# me_433_hw2.net
KiCad netlist of a schematic drawn in EAGLE
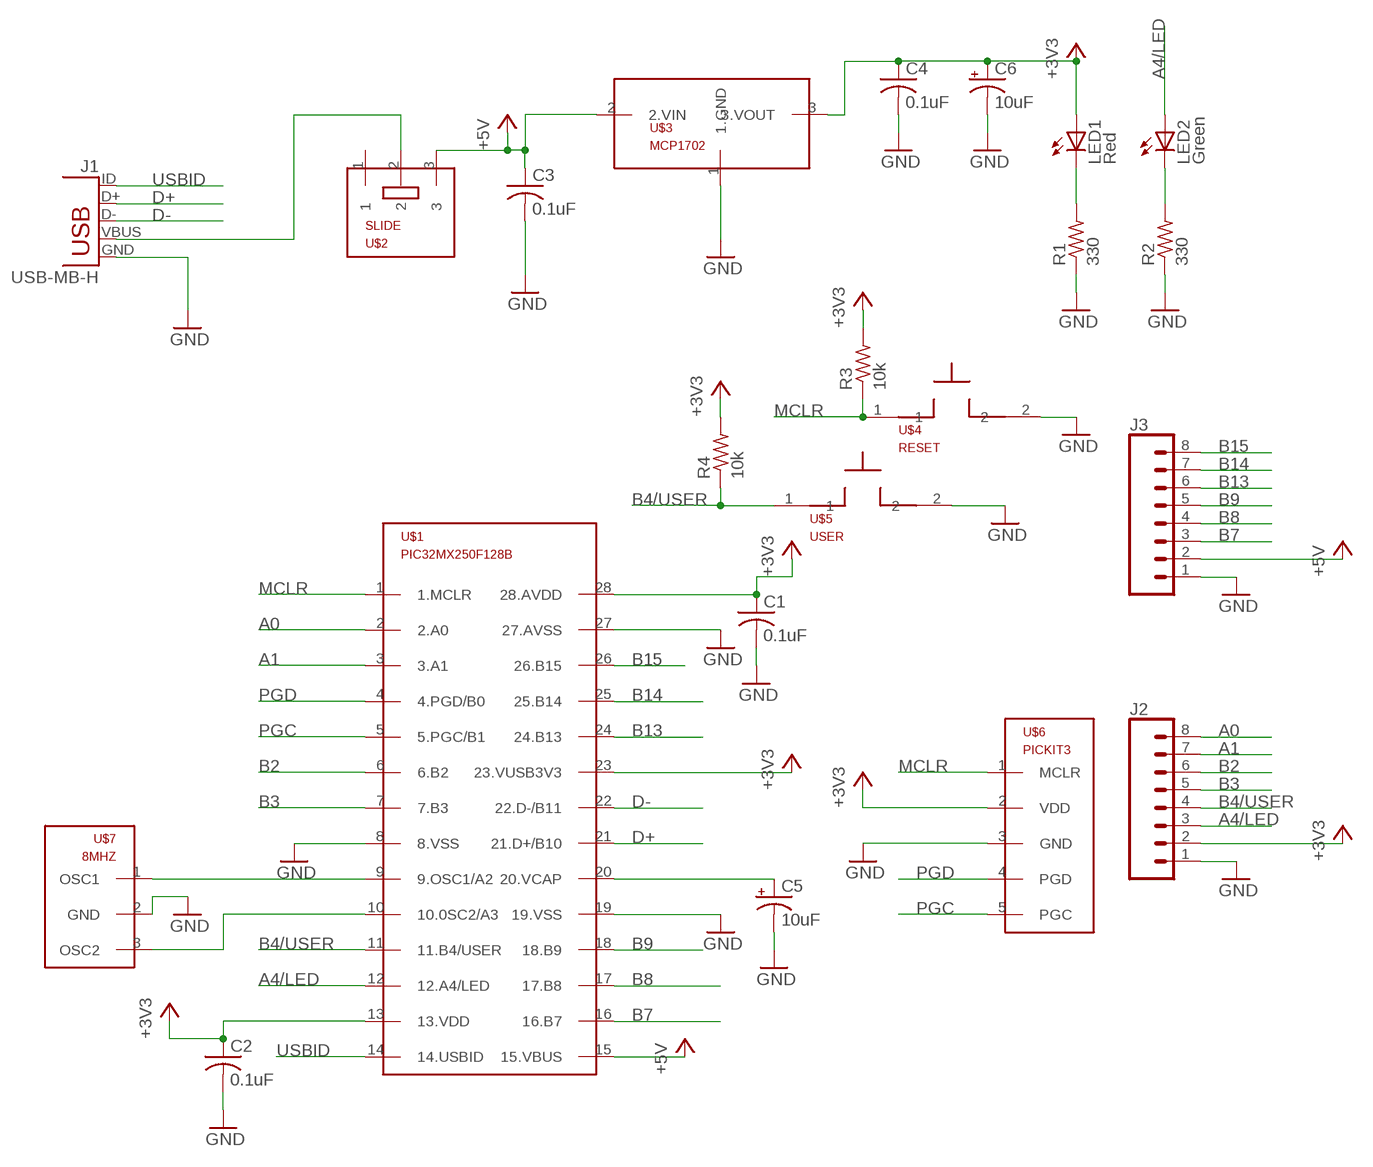
[diagram p0: schematic, sheet 1]

(export (version "E")
  (design (tool "Eeschema 10.0.6"))
  (components
    (comp (ref "C1")
      (value "0.1uF")
      (footprint "eagle-import:C025-025X050")
      (libsource (lib "eagle-import") (part "C-US025-025X050"))
    )
    (comp (ref "C2")
      (value "0.1uF")
      (footprint "eagle-import:C025-025X050")
      (libsource (lib "eagle-import") (part "C-US025-025X050"))
    )
    (comp (ref "C3")
      (value "0.1uF")
      (footprint "eagle-import:C025-025X050")
      (libsource (lib "eagle-import") (part "C-US025-025X050"))
    )
    (comp (ref "C4")
      (value "0.1uF")
      (footprint "eagle-import:C025-025X050")
      (libsource (lib "eagle-import") (part "C-US025-025X050"))
    )
    (comp (ref "C5")
      (value "10uF")
      (footprint "eagle-import:B45181B")
      (libsource (lib "eagle-import") (part "CPOL-USB45181B"))
    )
    (comp (ref "C6")
      (value "10uF")
      (footprint "eagle-import:B45181B")
      (libsource (lib "eagle-import") (part "CPOL-USB45181B"))
    )
    (comp (ref "J1")
      (value "USB-MB-H")
      (footprint "eagle-import:USB-MB-H")
      (libsource (lib "eagle-import") (part "USB-MB-H"))
    )
    (comp (ref "J2")
      (value "CONN_08")
      (footprint "eagle-import:1X08")
      (libsource (lib "eagle-import") (part "CONN_08"))
    )
    (comp (ref "J3")
      (value "CONN_08")
      (footprint "eagle-import:1X08")
      (libsource (lib "eagle-import") (part "CONN_08"))
    )
    (comp (ref "LED1")
      (value "Red")
      (footprint "eagle-import:LED3MM")
      (libsource (lib "eagle-import") (part "LED3MM"))
    )
    (comp (ref "LED2")
      (value "Green")
      (footprint "eagle-import:LED3MM")
      (libsource (lib "eagle-import") (part "LED3MM"))
    )
    (comp (ref "R1")
      (value "330")
      (footprint "eagle-import:0207_10")
      (libsource (lib "eagle-import") (part "R-US_0207/10"))
    )
    (comp (ref "R2")
      (value "330")
      (footprint "eagle-import:0207_10")
      (libsource (lib "eagle-import") (part "R-US_0207/10"))
    )
    (comp (ref "R3")
      (value "10k")
      (footprint "eagle-import:0207_10")
      (libsource (lib "eagle-import") (part "R-US_0207/10"))
    )
    (comp (ref "R4")
      (value "10k")
      (footprint "eagle-import:0207_10")
      (libsource (lib "eagle-import") (part "R-US_0207/10"))
    )
    (comp (ref "U$1")
      (value "PIC32MX250F128B")
      (footprint "eagle-import:DIL28-3")
      (libsource (lib "eagle-import") (part "PIC32MX250F128B"))
    )
    (comp (ref "U$2")
      (value "SLIDE")
      (footprint "eagle-import:SLIDE")
      (libsource (lib "eagle-import") (part "SLIDE"))
    )
    (comp (ref "U$3")
      (value "MCP1702")
      (footprint "eagle-import:TO92")
      (libsource (lib "eagle-import") (part "MCP1702"))
    )
    (comp (ref "U$4")
      (value "RESET")
      (footprint "eagle-import:PB")
      (libsource (lib "eagle-import") (part "PB"))
    )
    (comp (ref "U$5")
      (value "USER")
      (footprint "eagle-import:PB")
      (libsource (lib "eagle-import") (part "PB"))
    )
    (comp (ref "U$6")
      (value "PICKIT3")
      (footprint "eagle-import:1X05")
      (libsource (lib "eagle-import") (part "PICKIT3"))
    )
    (comp (ref "U$7")
      (value "8MHZ")
      (footprint "eagle-import:OSC")
      (libsource (lib "eagle-import") (part "OSC"))
    )
  )
  (nets
    (net (code "1") (name "+3V3") (class "Default")
      (node (ref "C1") (pin "1") (pinfunction "1_1") (pintype "passive"))
      (node (ref "C2") (pin "1") (pinfunction "1_1") (pintype "passive"))
      (node (ref "C4") (pin "1") (pinfunction "1_1") (pintype "passive"))
      (node (ref "C6") (pin "+") (pinfunction "+_+") (pintype "passive"))
      (node (ref "J2") (pin "2") (pinfunction "2_2") (pintype "passive"))
      (node (ref "LED1") (pin "A") (pinfunction "A_A") (pintype "passive"))
      (node (ref "R3") (pin "2") (pinfunction "2_2") (pintype "passive"))
      (node (ref "R4") (pin "2") (pinfunction "2_2") (pintype "passive"))
      (node (ref "U$1") (pin "13") (pinfunction "13.VDD_13") (pintype "bidirectional"))
      (node (ref "U$1") (pin "23") (pinfunction "23.VUSB3V3_23") (pintype "bidirectional"))
      (node (ref "U$1") (pin "28") (pinfunction "28.AVDD_28") (pintype "bidirectional"))
      (node (ref "U$3") (pin "3") (pinfunction "3.VOUT_3") (pintype "bidirectional"))
      (node (ref "U$6") (pin "2") (pinfunction "VDD_2") (pintype "bidirectional"))
    )
    (net (code "2") (name "+5V") (class "Default")
      (node (ref "C3") (pin "1") (pinfunction "1_1") (pintype "passive"))
      (node (ref "J3") (pin "2") (pinfunction "2_2") (pintype "passive"))
      (node (ref "U$1") (pin "15") (pinfunction "15.VBUS_15") (pintype "bidirectional"))
      (node (ref "U$2") (pin "3") (pinfunction "3_3") (pintype "bidirectional"))
      (node (ref "U$3") (pin "2") (pinfunction "2.VIN_2") (pintype "bidirectional"))
    )
    (net (code "3") (name "/A0") (class "Default")
      (node (ref "J2") (pin "8") (pinfunction "8_8") (pintype "passive"))
      (node (ref "U$1") (pin "2") (pinfunction "2.A0_2") (pintype "bidirectional"))
    )
    (net (code "4") (name "/A1") (class "Default")
      (node (ref "J2") (pin "7") (pinfunction "7_7") (pintype "passive"))
      (node (ref "U$1") (pin "3") (pinfunction "3.A1_3") (pintype "bidirectional"))
    )
    (net (code "5") (name "/A4{slash}LED") (class "Default")
      (node (ref "J2") (pin "3") (pinfunction "3_3") (pintype "passive"))
      (node (ref "LED2") (pin "A") (pinfunction "A_A") (pintype "passive"))
      (node (ref "U$1") (pin "12") (pinfunction "12.A4/LED_12") (pintype "bidirectional"))
    )
    (net (code "6") (name "/B2") (class "Default")
      (node (ref "J2") (pin "6") (pinfunction "6_6") (pintype "passive"))
      (node (ref "U$1") (pin "6") (pinfunction "6.B2_6") (pintype "bidirectional"))
    )
    (net (code "7") (name "/B3") (class "Default")
      (node (ref "J2") (pin "5") (pinfunction "5_5") (pintype "passive"))
      (node (ref "U$1") (pin "7") (pinfunction "7.B3_7") (pintype "bidirectional"))
    )
    (net (code "8") (name "/B4{slash}USER") (class "Default")
      (node (ref "J2") (pin "4") (pinfunction "4_4") (pintype "passive"))
      (node (ref "R4") (pin "1") (pinfunction "1_1") (pintype "passive"))
      (node (ref "U$1") (pin "11") (pinfunction "11.B4/USER_11") (pintype "bidirectional"))
      (node (ref "U$5") (pin "1") (pinfunction "1_1") (pintype "bidirectional"))
    )
    (net (code "9") (name "/B7") (class "Default")
      (node (ref "J3") (pin "3") (pinfunction "3_3") (pintype "passive"))
      (node (ref "U$1") (pin "16") (pinfunction "16.B7_16") (pintype "bidirectional"))
    )
    (net (code "10") (name "/B8") (class "Default")
      (node (ref "J3") (pin "4") (pinfunction "4_4") (pintype "passive"))
      (node (ref "U$1") (pin "17") (pinfunction "17.B8_17") (pintype "bidirectional"))
    )
    (net (code "11") (name "/B9") (class "Default")
      (node (ref "J3") (pin "5") (pinfunction "5_5") (pintype "passive"))
      (node (ref "U$1") (pin "18") (pinfunction "18.B9_18") (pintype "bidirectional"))
    )
    (net (code "12") (name "/B13") (class "Default")
      (node (ref "J3") (pin "6") (pinfunction "6_6") (pintype "passive"))
      (node (ref "U$1") (pin "24") (pinfunction "24.B13_24") (pintype "bidirectional"))
    )
    (net (code "13") (name "/B14") (class "Default")
      (node (ref "J3") (pin "7") (pinfunction "7_7") (pintype "passive"))
      (node (ref "U$1") (pin "25") (pinfunction "25.B14_25") (pintype "bidirectional"))
    )
    (net (code "14") (name "/B15") (class "Default")
      (node (ref "J3") (pin "8") (pinfunction "8_8") (pintype "passive"))
      (node (ref "U$1") (pin "26") (pinfunction "26.B15_26") (pintype "bidirectional"))
    )
    (net (code "15") (name "/D+") (class "Default")
      (node (ref "J1") (pin "D+") (pinfunction "D+_D+") (pintype "bidirectional"))
      (node (ref "U$1") (pin "21") (pinfunction "21.D+/B10_21") (pintype "bidirectional"))
    )
    (net (code "16") (name "/D-") (class "Default")
      (node (ref "J1") (pin "D-") (pinfunction "D-_D-") (pintype "bidirectional"))
      (node (ref "U$1") (pin "22") (pinfunction "22.D-/B11_22") (pintype "bidirectional"))
    )
    (net (code "17") (name "/MCLR") (class "Default")
      (node (ref "R3") (pin "1") (pinfunction "1_1") (pintype "passive"))
      (node (ref "U$1") (pin "1") (pinfunction "1.MCLR_1") (pintype "bidirectional"))
      (node (ref "U$4") (pin "1") (pinfunction "1_1") (pintype "bidirectional"))
      (node (ref "U$6") (pin "1") (pinfunction "MCLR_1") (pintype "bidirectional"))
    )
    (net (code "18") (name "/PGC") (class "Default")
      (node (ref "U$1") (pin "5") (pinfunction "5.PGC/B1_5") (pintype "bidirectional"))
      (node (ref "U$6") (pin "5") (pinfunction "PGC_5") (pintype "bidirectional"))
    )
    (net (code "19") (name "/PGD") (class "Default")
      (node (ref "U$1") (pin "4") (pinfunction "4.PGD/B0_4") (pintype "bidirectional"))
      (node (ref "U$6") (pin "4") (pinfunction "PGD_4") (pintype "bidirectional"))
    )
    (net (code "20") (name "/USBID") (class "Default")
      (node (ref "J1") (pin "ID") (pinfunction "ID_ID") (pintype "bidirectional"))
      (node (ref "U$1") (pin "14") (pinfunction "14.USBID_14") (pintype "bidirectional"))
    )
    (net (code "21") (name "GND") (class "Default")
      (node (ref "C1") (pin "2") (pinfunction "2_2") (pintype "passive"))
      (node (ref "C2") (pin "2") (pinfunction "2_2") (pintype "passive"))
      (node (ref "C3") (pin "2") (pinfunction "2_2") (pintype "passive"))
      (node (ref "C4") (pin "2") (pinfunction "2_2") (pintype "passive"))
      (node (ref "C5") (pin "-") (pinfunction "-_-") (pintype "passive"))
      (node (ref "C6") (pin "-") (pinfunction "-_-") (pintype "passive"))
      (node (ref "J1") (pin "GND") (pinfunction "GND_GND") (pintype "bidirectional"))
      (node (ref "J2") (pin "1") (pinfunction "1_1") (pintype "passive"))
      (node (ref "J3") (pin "1") (pinfunction "1_1") (pintype "passive"))
      (node (ref "R1") (pin "1") (pinfunction "1_1") (pintype "passive"))
      (node (ref "R2") (pin "1") (pinfunction "1_1") (pintype "passive"))
      (node (ref "U$1") (pin "19") (pinfunction "19.VSS_19") (pintype "bidirectional"))
      (node (ref "U$1") (pin "27") (pinfunction "27.AVSS_27") (pintype "bidirectional"))
      (node (ref "U$1") (pin "8") (pinfunction "8.VSS_8") (pintype "bidirectional"))
      (node (ref "U$3") (pin "1") (pinfunction "1.GND_1") (pintype "bidirectional"))
      (node (ref "U$4") (pin "2") (pinfunction "2_2") (pintype "bidirectional"))
      (node (ref "U$5") (pin "2") (pinfunction "2_2") (pintype "bidirectional"))
      (node (ref "U$6") (pin "3") (pinfunction "GND_3") (pintype "bidirectional"))
      (node (ref "U$7") (pin "2") (pinfunction "GND_2") (pintype "bidirectional"))
    )
    (net (code "22") (name "Net-(J1-PadVBUS)") (class "Default")
      (node (ref "J1") (pin "VBUS") (pinfunction "VBUS_VBUS") (pintype "bidirectional"))
      (node (ref "U$2") (pin "2") (pinfunction "2_2") (pintype "bidirectional"))
    )
    (net (code "23") (name "Net-(LED1-C)") (class "Default")
      (node (ref "LED1") (pin "K") (pinfunction "C_K") (pintype "passive"))
      (node (ref "R1") (pin "2") (pinfunction "2_2") (pintype "passive"))
    )
    (net (code "24") (name "Net-(LED2-C)") (class "Default")
      (node (ref "LED2") (pin "K") (pinfunction "C_K") (pintype "passive"))
      (node (ref "R2") (pin "2") (pinfunction "2_2") (pintype "passive"))
    )
    (net (code "25") (name "Net-(U$1-9.OSC1{slash}A2)") (class "Default")
      (node (ref "U$1") (pin "9") (pinfunction "9.OSC1/A2_9") (pintype "bidirectional"))
      (node (ref "U$7") (pin "1") (pinfunction "OSC1_1") (pintype "bidirectional"))
    )
    (net (code "26") (name "Net-(U$1-10.0SC2{slash}A3)") (class "Default")
      (node (ref "U$1") (pin "10") (pinfunction "10.0SC2/A3_10") (pintype "bidirectional"))
      (node (ref "U$7") (pin "3") (pinfunction "OSC2_3") (pintype "bidirectional"))
    )
    (net (code "27") (name "Net-(U$1-20.VCAP)") (class "Default")
      (node (ref "C5") (pin "+") (pinfunction "+_+") (pintype "passive"))
      (node (ref "U$1") (pin "20") (pinfunction "20.VCAP_20") (pintype "bidirectional"))
    )
    (net (code "28") (name "unconnected-(U$2-Pad1)") (class "Default")
      (node (ref "U$2") (pin "1") (pinfunction "1_1") (pintype "bidirectional"))
    )
  )
)
